# power.net
KiCad netlist of a schematic drawn in Altium Designer
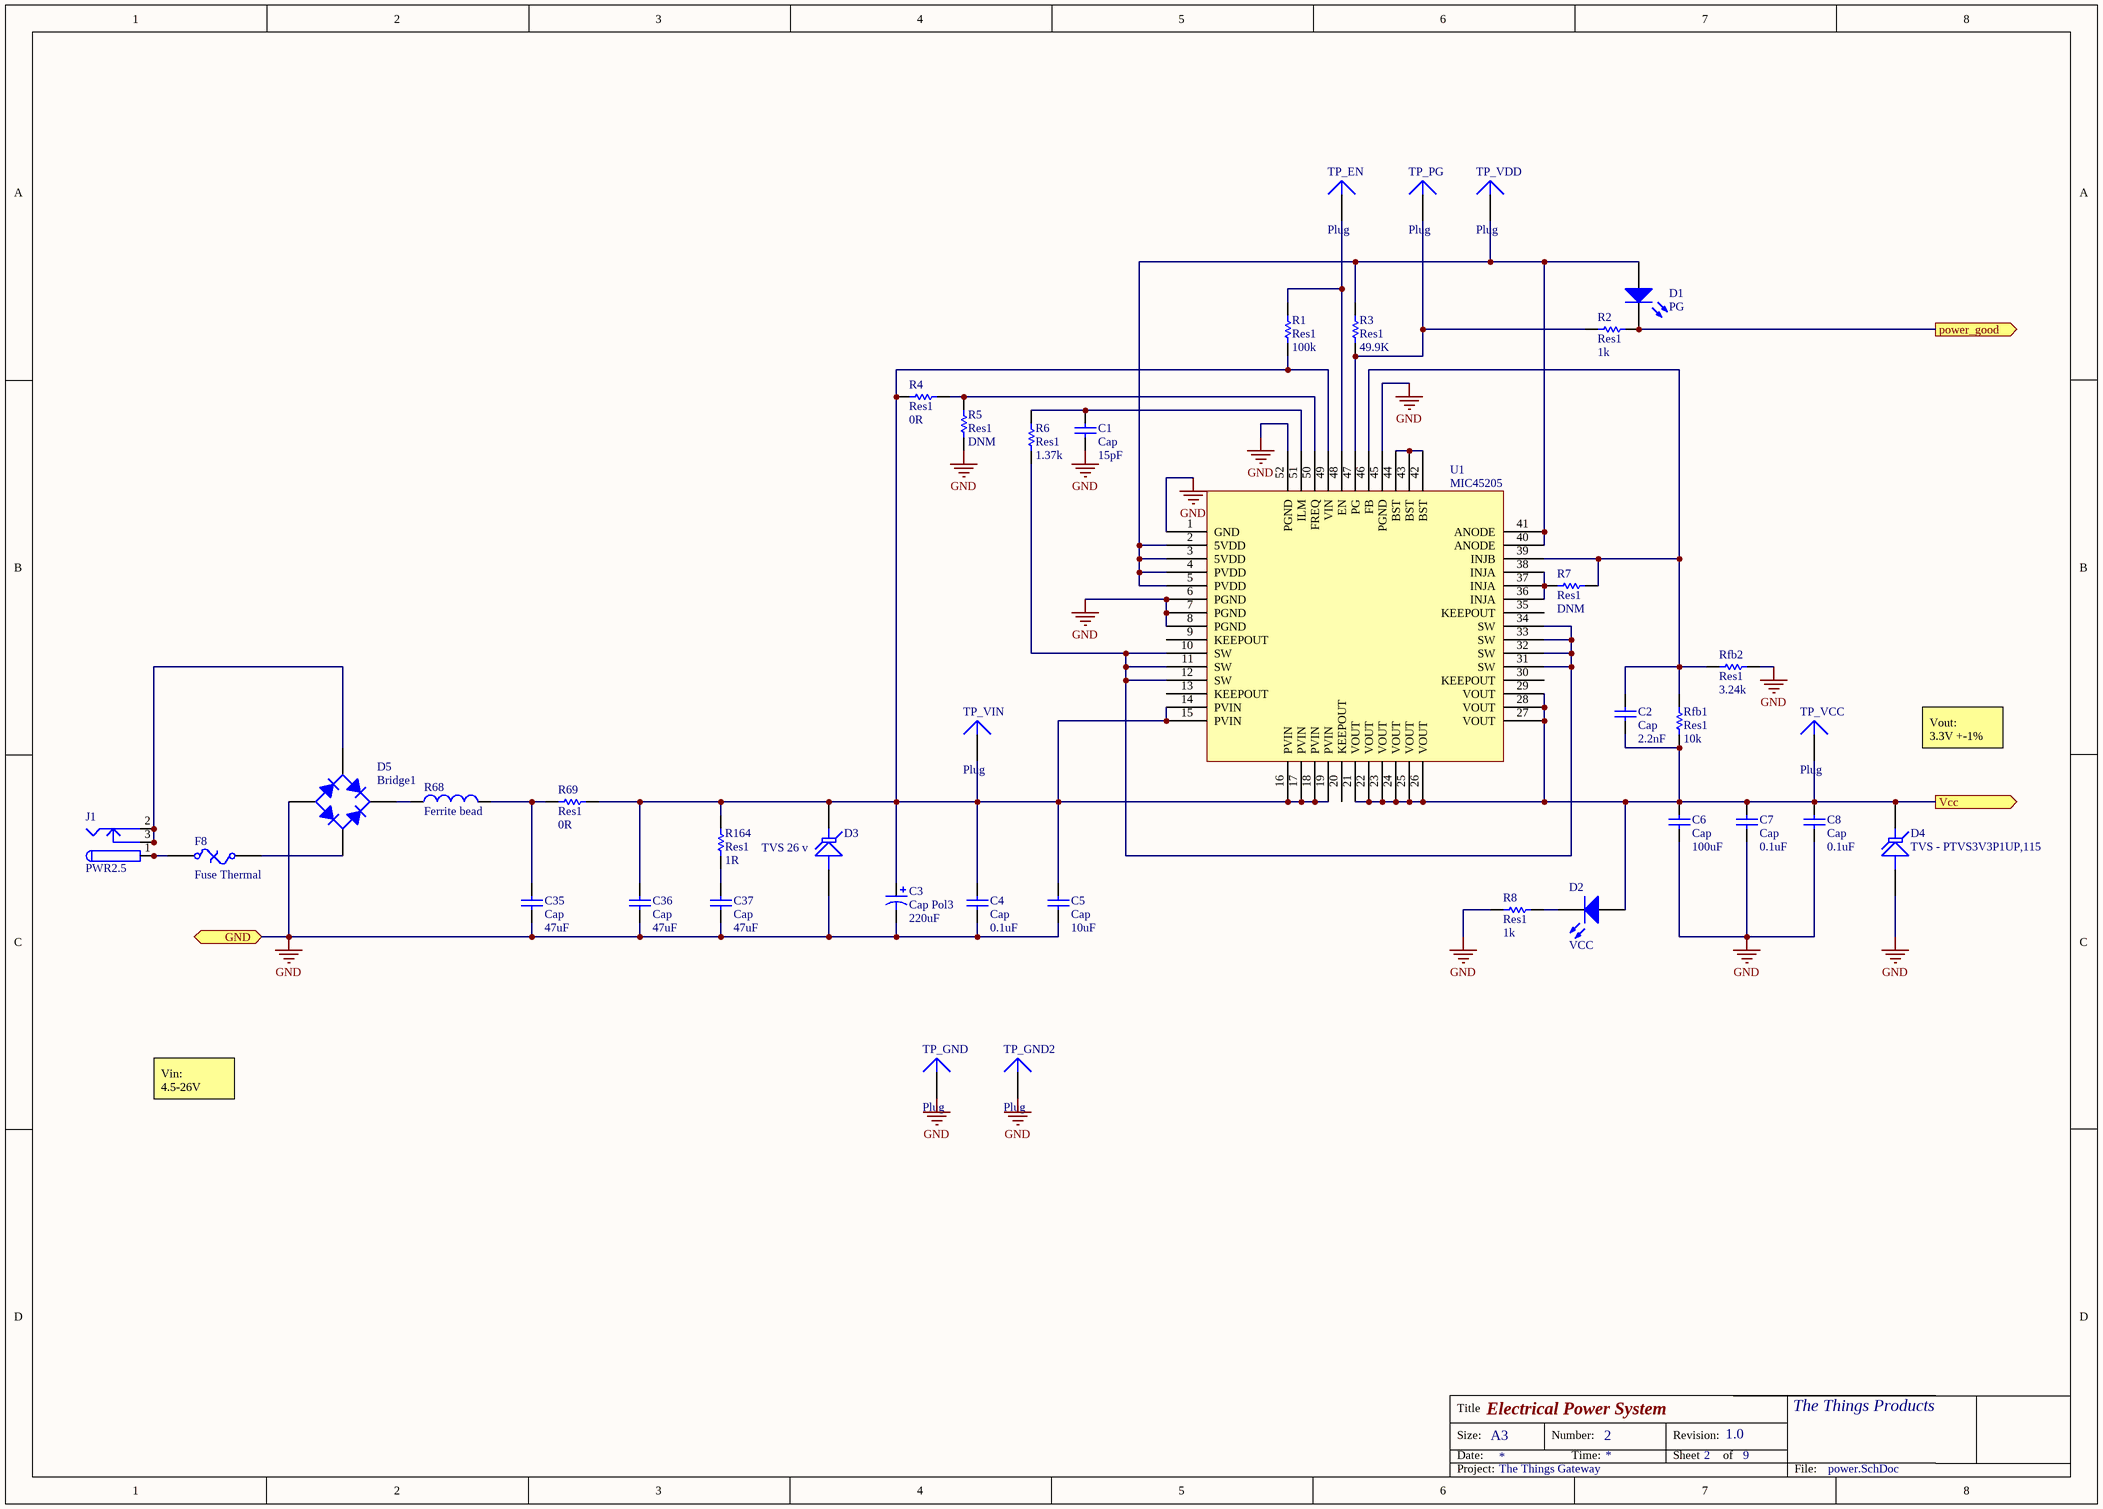
[diagram p0: power.SchDoc]

(export (version "E")
  (design (tool "Eeschema 10.0.6"))
  (components
    (comp (ref "C1")
      (value "Cap")
      (footprint "C0603")
      (description "Capacitor")
      (fields (field (name "ALTIUM_VALUE") "15pF") (field (name "PUBLISHER") "Altium Limited"))
      (libsource (lib "any") (part "Cap"))
    )
    (comp (ref "C2")
      (value "Cap")
      (footprint "C0603")
      (description "Capacitor")
      (fields (field (name "ALTIUM_VALUE") "2.2nF") (field (name "PUBLISHER") "Altium Limited"))
      (libsource (lib "any") (part "Cap"))
    )
    (comp (ref "C3")
      (value "Cap Pol3")
      (footprint "SMD_CAP_10x7.7mm_220uF - duplicate")
      (description "Polarized Capacitor (Surface Mount)")
      (fields (field (name "ALTIUM_VALUE") "220uF") (field (name "PUBLISHER") "Altium Limited"))
      (libsource (lib "Miscellaneous Devices") (part "Cap Pol3"))
    )
    (comp (ref "C4")
      (value "Cap")
      (footprint "C1206")
      (description "Capacitor")
      (fields (field (name "ALTIUM_VALUE") "0.1uF") (field (name "PUBLISHER") "Altium Limited"))
      (libsource (lib "any") (part "Cap"))
    )
    (comp (ref "C5")
      (value "Cap")
      (footprint "C1210")
      (description "Capacitor")
      (fields (field (name "ALTIUM_VALUE") "10uF") (field (name "PUBLISHER") "Altium Limited"))
      (libsource (lib "any") (part "Cap"))
    )
    (comp (ref "C6")
      (value "Cap")
      (footprint "C1210")
      (description "Capacitor")
      (fields (field (name "ALTIUM_VALUE") "100uF") (field (name "PUBLISHER") "Altium Limited"))
      (libsource (lib "any") (part "Cap"))
    )
    (comp (ref "C7")
      (value "Cap")
      (footprint "C1206")
      (description "Capacitor")
      (fields (field (name "ALTIUM_VALUE") "0.1uF") (field (name "PUBLISHER") "Altium Limited"))
      (libsource (lib "any") (part "Cap"))
    )
    (comp (ref "C8")
      (value "Cap")
      (footprint "C1206")
      (description "Capacitor")
      (fields (field (name "ALTIUM_VALUE") "0.1uF") (field (name "PUBLISHER") "Altium Limited"))
      (libsource (lib "any") (part "Cap"))
    )
    (comp (ref "C35")
      (value "Cap")
      (footprint "C1206")
      (description "Capacitor")
      (fields (field (name "ALTIUM_VALUE") "47uF") (field (name "PUBLISHER") "Altium Limited"))
      (libsource (lib "any") (part "Cap"))
    )
    (comp (ref "C36")
      (value "Cap")
      (footprint "C1206")
      (description "Capacitor")
      (fields (field (name "ALTIUM_VALUE") "47uF") (field (name "PUBLISHER") "Altium Limited"))
      (libsource (lib "any") (part "Cap"))
    )
    (comp (ref "C37")
      (value "Cap")
      (footprint "C0603")
      (description "Capacitor")
      (fields (field (name "ALTIUM_VALUE") "47uF") (field (name "PUBLISHER") "Altium Limited"))
      (libsource (lib "any") (part "Cap"))
    )
    (comp (ref "D1")
      (value "PG")
      (footprint "C0603")
      (description "Typical INFRARED GaAs LED")
      (fields (field (name "PUBLISHER") "Altium Limited"))
      (libsource (lib "any") (part "LED0"))
    )
    (comp (ref "D2")
      (value "VCC")
      (footprint "C0603")
      (description "Typical INFRARED GaAs LED")
      (fields (field (name "PUBLISHER") "Altium Limited"))
      (libsource (lib "any") (part "LED0"))
    )
    (comp (ref "D3")
      (value "TVS 26 v")
      (footprint "SOD323")
      (description "Transient Voltage Suppression (TVS) Diode")
      (fields (field (name "PUBLISHER") "Altium Limited"))
      (libsource (lib "Miscellaneous Devices") (part "Tranzorb"))
    )
    (comp (ref "D4")
      (value "TVS - PTVS3V3P1UP,115")
      (footprint "SOD323")
      (description "Transient Voltage Suppression (TVS) Diode")
      (fields (field (name "PUBLISHER") "Altium Limited"))
      (libsource (lib "Miscellaneous Devices") (part "Tranzorb"))
    )
    (comp (ref "D5")
      (value "Bridge1")
      (footprint "4-SDIP")
      (description "Full Wave Diode Bridge")
      (fields (field (name "PUBLISHER") "Altium Limited"))
      (libsource (lib "TWTG_Development") (part "Bridge1"))
    )
    (comp (ref "F8")
      (value "Fuse Thermal")
      (footprint "1812-polyfuse")
      (description "Thermal Fuse")
      (fields (field (name "PUBLISHER") "Altium Limited"))
      (libsource (lib "Any") (part "Fuse Thermal"))
    )
    (comp (ref "J1")
      (value "PWR2.5")
      (footprint "KLD-0202")
      (description "Low Voltage Power Supply Connector")
      (fields (field (name "PUBLISHER") "Altium Limited"))
      (libsource (lib "Miscellaneous Connectors") (part "PWR2.5"))
    )
    (comp (ref "R1")
      (value "Res1")
      (footprint "R0603")
      (description "Resistor")
      (fields (field (name "ALTIUM_VALUE") "100k") (field (name "PUBLISHER") "Altium Limited"))
      (libsource (lib "Miscellaneous Devices") (part "Res1"))
    )
    (comp (ref "R2")
      (value "Res1")
      (footprint "R0603")
      (description "Resistor")
      (fields (field (name "ALTIUM_VALUE") "1k") (field (name "PUBLISHER") "Altium Limited"))
      (libsource (lib "Miscellaneous Devices") (part "Res1"))
    )
    (comp (ref "R3")
      (value "Res1")
      (footprint "R0603")
      (description "Resistor")
      (fields (field (name "ALTIUM_VALUE") "49.9K") (field (name "PUBLISHER") "Altium Limited"))
      (libsource (lib "Miscellaneous Devices") (part "Res1"))
    )
    (comp (ref "R4")
      (value "Res1")
      (footprint "R0603")
      (description "Resistor")
      (fields (field (name "ALTIUM_VALUE") "0R") (field (name "PUBLISHER") "Altium Limited"))
      (libsource (lib "Miscellaneous Devices") (part "Res1"))
    )
    (comp (ref "R5")
      (value "Res1")
      (footprint "R0603")
      (description "Resistor")
      (fields (field (name "ALTIUM_VALUE") "DNM") (field (name "PUBLISHER") "Altium Limited"))
      (libsource (lib "Miscellaneous Devices") (part "Res1"))
    )
    (comp (ref "R6")
      (value "Res1")
      (footprint "R0603")
      (description "Resistor")
      (fields (field (name "ALTIUM_VALUE") "1.37k") (field (name "PUBLISHER") "Altium Limited"))
      (libsource (lib "Miscellaneous Devices") (part "Res1"))
    )
    (comp (ref "R7")
      (value "Res1")
      (footprint "R0603")
      (description "Resistor")
      (fields (field (name "ALTIUM_VALUE") "DNM") (field (name "PUBLISHER") "Altium Limited"))
      (libsource (lib "Miscellaneous Devices") (part "Res1"))
    )
    (comp (ref "R8")
      (value "Res1")
      (footprint "R0603")
      (description "Resistor")
      (fields (field (name "ALTIUM_VALUE") "1k") (field (name "PUBLISHER") "Altium Limited"))
      (libsource (lib "Miscellaneous Devices") (part "Res1"))
    )
    (comp (ref "R68")
      (value "Ferrite bead")
      (footprint "R0603")
      (description "Inductor")
      (fields (field (name "PUBLISHER") "Altium Limited"))
      (libsource (lib "Miscellaneous Devices") (part "Inductor"))
    )
    (comp (ref "R69")
      (value "Res1")
      (footprint "R0603")
      (description "Resistor")
      (fields (field (name "ALTIUM_VALUE") "0R") (field (name "PUBLISHER") "Altium Limited"))
      (libsource (lib "Miscellaneous Devices") (part "Res1"))
    )
    (comp (ref "R164")
      (value "Res1")
      (footprint "R0603")
      (description "Resistor")
      (fields (field (name "ALTIUM_VALUE") "1R") (field (name "PUBLISHER") "Altium Limited"))
      (libsource (lib "Miscellaneous Devices") (part "Res1"))
    )
    (comp (ref "Rfb1")
      (value "Res1")
      (footprint "R0603")
      (description "Resistor")
      (fields (field (name "ALTIUM_VALUE") "10k") (field (name "PUBLISHER") "Altium Limited"))
      (libsource (lib "Miscellaneous Devices") (part "Res1"))
    )
    (comp (ref "Rfb2")
      (value "Res1")
      (footprint "R0603")
      (description "Resistor")
      (fields (field (name "ALTIUM_VALUE") "3.24k") (field (name "PUBLISHER") "Altium Limited"))
      (libsource (lib "Miscellaneous Devices") (part "Res1"))
    )
    (comp (ref "TP_EN")
      (value "Plug")
      (footprint "PIN1")
      (fields (field (name "PUBLISHER") "Altium Limited"))
      (libsource (lib "Miscellaneous Connectors") (part "Plug"))
    )
    (comp (ref "TP_GND")
      (value "Plug")
      (footprint "PIN1")
      (fields (field (name "PUBLISHER") "Altium Limited"))
      (libsource (lib "Miscellaneous Connectors") (part "Plug"))
    )
    (comp (ref "TP_GND2")
      (value "Plug")
      (footprint "PIN1")
      (fields (field (name "PUBLISHER") "Altium Limited"))
      (libsource (lib "Miscellaneous Connectors") (part "Plug"))
    )
    (comp (ref "TP_PG")
      (value "Plug")
      (footprint "PIN1")
      (fields (field (name "PUBLISHER") "Altium Limited"))
      (libsource (lib "Miscellaneous Connectors") (part "Plug"))
    )
    (comp (ref "TP_VCC")
      (value "Plug")
      (footprint "PIN1")
      (fields (field (name "PUBLISHER") "Altium Limited"))
      (libsource (lib "Miscellaneous Connectors") (part "Plug"))
    )
    (comp (ref "TP_VDD")
      (value "Plug")
      (footprint "PIN1")
      (fields (field (name "PUBLISHER") "Altium Limited"))
      (libsource (lib "Miscellaneous Connectors") (part "Plug"))
    )
    (comp (ref "TP_VIN")
      (value "Plug")
      (footprint "PIN1")
      (fields (field (name "PUBLISHER") "Altium Limited"))
      (libsource (lib "Miscellaneous Connectors") (part "Plug"))
    )
    (comp (ref "U1")
      (value "MIC45205")
      (footprint "45205 Thermaly Enhanced")
      (description "MICREL45205 DC/DC Converter")
      (libsource (lib "ttn_schematic_library") (part "MIC45205"))
    )
  )
  (nets
    (net (code "1") (name "/Vcc") (class "Default")
      (node (ref "C2") (pin "1") (pinfunction "1_1") (pintype "passive"))
      (node (ref "C6") (pin "2") (pinfunction "2_2") (pintype "passive"))
      (node (ref "C7") (pin "2") (pinfunction "2_2") (pintype "passive"))
      (node (ref "C8") (pin "2") (pinfunction "2_2") (pintype "passive"))
      (node (ref "D2") (pin "1") (pinfunction "A_1") (pintype "passive"))
      (node (ref "D4") (pin "2") (pinfunction "K_2") (pintype "passive"))
      (node (ref "Rfb1") (pin "1") (pinfunction "1_1") (pintype "passive"))
      (node (ref "TP_VCC") (pin "1") (pinfunction "1_1") (pintype "passive"))
      (node (ref "U1") (pin "21") (pinfunction "VOUT_21") (pintype "passive"))
      (node (ref "U1") (pin "22") (pinfunction "VOUT_22") (pintype "passive"))
      (node (ref "U1") (pin "23") (pinfunction "VOUT_23") (pintype "passive"))
      (node (ref "U1") (pin "24") (pinfunction "VOUT_24") (pintype "passive"))
      (node (ref "U1") (pin "25") (pinfunction "VOUT_25") (pintype "passive"))
      (node (ref "U1") (pin "26") (pinfunction "VOUT_26") (pintype "passive"))
      (node (ref "U1") (pin "27") (pinfunction "VOUT_27") (pintype "passive"))
      (node (ref "U1") (pin "28") (pinfunction "VOUT_28") (pintype "passive"))
      (node (ref "U1") (pin "29") (pinfunction "VOUT_29") (pintype "passive"))
    )
    (net (code "2") (name "/power_good") (class "Default")
      (node (ref "D1") (pin "2") (pinfunction "K_2") (pintype "passive"))
      (node (ref "R2") (pin "1") (pinfunction "1_1") (pintype "passive"))
    )
    (net (code "3") (name "GND") (class "Default")
      (node (ref "C1") (pin "1") (pinfunction "1_1") (pintype "passive"))
      (node (ref "C3") (pin "2") (pinfunction "2_2") (pintype "passive"))
      (node (ref "C35") (pin "1") (pinfunction "1_1") (pintype "passive"))
      (node (ref "C36") (pin "1") (pinfunction "1_1") (pintype "passive"))
      (node (ref "C37") (pin "1") (pinfunction "1_1") (pintype "passive"))
      (node (ref "C4") (pin "1") (pinfunction "1_1") (pintype "passive"))
      (node (ref "C5") (pin "1") (pinfunction "1_1") (pintype "passive"))
      (node (ref "C6") (pin "1") (pinfunction "1_1") (pintype "passive"))
      (node (ref "C7") (pin "1") (pinfunction "1_1") (pintype "passive"))
      (node (ref "C8") (pin "1") (pinfunction "1_1") (pintype "passive"))
      (node (ref "D3") (pin "1") (pinfunction "A_1") (pintype "passive"))
      (node (ref "D4") (pin "1") (pinfunction "A_1") (pintype "passive"))
      (node (ref "D5") (pin "2") (pinfunction "A_2") (pintype "passive"))
      (node (ref "R5") (pin "2") (pinfunction "2_2") (pintype "passive"))
      (node (ref "R8") (pin "1") (pinfunction "1_1") (pintype "passive"))
      (node (ref "Rfb2") (pin "1") (pinfunction "1_1") (pintype "passive"))
      (node (ref "TP_GND") (pin "1") (pinfunction "1_1") (pintype "passive"))
      (node (ref "TP_GND2") (pin "1") (pinfunction "1_1") (pintype "passive"))
      (node (ref "U1") (pin "1") (pinfunction "GND_1") (pintype "passive"))
      (node (ref "U1") (pin "45") (pinfunction "PGND_45") (pintype "passive"))
      (node (ref "U1") (pin "52") (pinfunction "PGND_52") (pintype "passive"))
      (node (ref "U1") (pin "6") (pinfunction "PGND_6") (pintype "passive"))
      (node (ref "U1") (pin "7") (pinfunction "PGND_7") (pintype "passive"))
      (node (ref "U1") (pin "8") (pinfunction "PGND_8") (pintype "passive"))
    )
    (net (code "4") (name "Net-(C35-Pad2)") (class "Default")
      (node (ref "C35") (pin "2") (pinfunction "2_2") (pintype "passive"))
      (node (ref "R68") (pin "2") (pinfunction "2_2") (pintype "passive"))
      (node (ref "R69") (pin "2") (pinfunction "2_2") (pintype "passive"))
    )
    (net (code "5") (name "Net-(C37-Pad2)") (class "Default")
      (node (ref "C37") (pin "2") (pinfunction "2_2") (pintype "passive"))
      (node (ref "R164") (pin "2") (pinfunction "2_2") (pintype "passive"))
    )
    (net (code "6") (name "Net-(D1-A)") (class "Default")
      (node (ref "D1") (pin "1") (pinfunction "A_1") (pintype "passive"))
      (node (ref "R3") (pin "1") (pinfunction "1_1") (pintype "passive"))
      (node (ref "TP_VDD") (pin "1") (pinfunction "1_1") (pintype "passive"))
      (node (ref "U1") (pin "2") (pinfunction "5VDD_2") (pintype "passive"))
      (node (ref "U1") (pin "3") (pinfunction "5VDD_3") (pintype "passive"))
      (node (ref "U1") (pin "4") (pinfunction "PVDD_4") (pintype "passive"))
      (node (ref "U1") (pin "40") (pinfunction "ANODE_40") (pintype "passive"))
      (node (ref "U1") (pin "41") (pinfunction "ANODE_41") (pintype "passive"))
      (node (ref "U1") (pin "5") (pinfunction "PVDD_5") (pintype "passive"))
    )
    (net (code "7") (name "Net-(D2-K)") (class "Default")
      (node (ref "D2") (pin "2") (pinfunction "K_2") (pintype "passive"))
      (node (ref "R8") (pin "2") (pinfunction "2_2") (pintype "passive"))
    )
    (net (code "8") (name "Net-(D3-K)") (class "Default")
      (node (ref "C3") (pin "1") (pinfunction "1_1") (pintype "passive"))
      (node (ref "C36") (pin "2") (pinfunction "2_2") (pintype "passive"))
      (node (ref "C4") (pin "2") (pinfunction "2_2") (pintype "passive"))
      (node (ref "C5") (pin "2") (pinfunction "2_2") (pintype "passive"))
      (node (ref "D3") (pin "2") (pinfunction "K_2") (pintype "passive"))
      (node (ref "R1") (pin "1") (pinfunction "1_1") (pintype "passive"))
      (node (ref "R164") (pin "1") (pinfunction "1_1") (pintype "passive"))
      (node (ref "R4") (pin "2") (pinfunction "2_2") (pintype "passive"))
      (node (ref "R69") (pin "1") (pinfunction "1_1") (pintype "passive"))
      (node (ref "TP_VIN") (pin "1") (pinfunction "1_1") (pintype "passive"))
      (node (ref "U1") (pin "14") (pinfunction "PVIN_14") (pintype "passive"))
      (node (ref "U1") (pin "15") (pinfunction "PVIN_15") (pintype "passive"))
      (node (ref "U1") (pin "16") (pinfunction "PVIN_16") (pintype "passive"))
      (node (ref "U1") (pin "17") (pinfunction "PVIN_17") (pintype "passive"))
      (node (ref "U1") (pin "18") (pinfunction "PVIN_18") (pintype "passive"))
      (node (ref "U1") (pin "19") (pinfunction "PVIN_19") (pintype "passive"))
      (node (ref "U1") (pin "49") (pinfunction "VIN_49") (pintype "passive"))
    )
    (net (code "9") (name "Net-(D5-C-Pad3)") (class "Default")
      (node (ref "D5") (pin "3") (pinfunction "C_3") (pintype "passive"))
      (node (ref "J1") (pin "2") (pinfunction "2_2") (pintype "power_in"))
      (node (ref "J1") (pin "2A") (pinfunction "2A_2A") (pintype "power_in"))
      (node (ref "J1") (pin "2B") (pinfunction "2B_2B") (pintype "power_in"))
      (node (ref "J1") (pin "3") (pinfunction "3_3") (pintype "power_in"))
      (node (ref "J1") (pin "3A") (pinfunction "3A_3A") (pintype "power_in"))
      (node (ref "J1") (pin "3B") (pinfunction "3B_3B") (pintype "power_in"))
    )
    (net (code "10") (name "Net-(D5-C-Pad4)") (class "Default")
      (node (ref "D5") (pin "4") (pinfunction "C_4") (pintype "passive"))
      (node (ref "F8") (pin "2") (pinfunction "2_2") (pintype "passive"))
    )
    (net (code "11") (name "Net-(D5-K)") (class "Default")
      (node (ref "D5") (pin "1") (pinfunction "K_1") (pintype "passive"))
      (node (ref "R68") (pin "1") (pinfunction "1_1") (pintype "passive"))
    )
    (net (code "12") (name "Net-(F8-Pad1)") (class "Default")
      (node (ref "F8") (pin "1") (pinfunction "1_1") (pintype "passive"))
      (node (ref "J1") (pin "1") (pinfunction "1_1") (pintype "power_in"))
      (node (ref "J1") (pin "1A") (pinfunction "1A_1A") (pintype "power_in"))
      (node (ref "J1") (pin "1B") (pinfunction "1B_1B") (pintype "power_in"))
    )
    (net (code "13") (name "Net-(R6-Pad1)") (class "Default")
      (node (ref "R6") (pin "1") (pinfunction "1_1") (pintype "passive"))
      (node (ref "U1") (pin "10") (pinfunction "SW_10") (pintype "passive"))
      (node (ref "U1") (pin "11") (pinfunction "SW_11") (pintype "passive"))
      (node (ref "U1") (pin "12") (pinfunction "SW_12") (pintype "passive"))
      (node (ref "U1") (pin "31") (pinfunction "SW_31") (pintype "passive"))
      (node (ref "U1") (pin "32") (pinfunction "SW_32") (pintype "passive"))
      (node (ref "U1") (pin "33") (pinfunction "SW_33") (pintype "passive"))
      (node (ref "U1") (pin "34") (pinfunction "SW_34") (pintype "passive"))
    )
    (net (code "14") (name "Net-(R7-Pad2)") (class "Default")
      (node (ref "R7") (pin "2") (pinfunction "2_2") (pintype "passive"))
      (node (ref "U1") (pin "36") (pinfunction "INJA_36") (pintype "passive"))
      (node (ref "U1") (pin "37") (pinfunction "INJA_37") (pintype "passive"))
      (node (ref "U1") (pin "38") (pinfunction "INJA_38") (pintype "passive"))
    )
    (net (code "15") (name "Net-(U1-BST-Pad42)") (class "Default")
      (node (ref "U1") (pin "42") (pinfunction "BST_42") (pintype "passive"))
      (node (ref "U1") (pin "43") (pinfunction "BST_43") (pintype "passive"))
      (node (ref "U1") (pin "44") (pinfunction "BST_44") (pintype "passive"))
    )
    (net (code "16") (name "Net-(U1-EN)") (class "Default")
      (node (ref "R1") (pin "2") (pinfunction "2_2") (pintype "passive"))
      (node (ref "TP_EN") (pin "1") (pinfunction "1_1") (pintype "passive"))
      (node (ref "U1") (pin "48") (pinfunction "EN_48") (pintype "passive"))
    )
    (net (code "17") (name "Net-(U1-FB)") (class "Default")
      (node (ref "C2") (pin "2") (pinfunction "2_2") (pintype "passive"))
      (node (ref "R7") (pin "1") (pinfunction "1_1") (pintype "passive"))
      (node (ref "Rfb1") (pin "2") (pinfunction "2_2") (pintype "passive"))
      (node (ref "Rfb2") (pin "2") (pinfunction "2_2") (pintype "passive"))
      (node (ref "U1") (pin "39") (pinfunction "INJB_39") (pintype "passive"))
      (node (ref "U1") (pin "46") (pinfunction "FB_46") (pintype "passive"))
    )
    (net (code "18") (name "Net-(U1-FREQ)") (class "Default")
      (node (ref "R4") (pin "1") (pinfunction "1_1") (pintype "passive"))
      (node (ref "R5") (pin "1") (pinfunction "1_1") (pintype "passive"))
      (node (ref "U1") (pin "50") (pinfunction "FREQ_50") (pintype "passive"))
    )
    (net (code "19") (name "Net-(U1-ILM)") (class "Default")
      (node (ref "C1") (pin "2") (pinfunction "2_2") (pintype "passive"))
      (node (ref "R6") (pin "2") (pinfunction "2_2") (pintype "passive"))
      (node (ref "U1") (pin "51") (pinfunction "ILM_51") (pintype "passive"))
    )
    (net (code "20") (name "Net-(U1-PG)") (class "Default")
      (node (ref "R2") (pin "2") (pinfunction "2_2") (pintype "passive"))
      (node (ref "R3") (pin "2") (pinfunction "2_2") (pintype "passive"))
      (node (ref "TP_PG") (pin "1") (pinfunction "1_1") (pintype "passive"))
      (node (ref "U1") (pin "47") (pinfunction "PG_47") (pintype "passive"))
    )
    (net (code "21") (name "unconnected-(U1-KEEPOUT-Pad9)") (class "Default")
      (node (ref "U1") (pin "9") (pinfunction "KEEPOUT_9") (pintype "passive"))
    )
    (net (code "22") (name "unconnected-(U1-KEEPOUT-Pad13)") (class "Default")
      (node (ref "U1") (pin "13") (pinfunction "KEEPOUT_13") (pintype "passive"))
    )
    (net (code "23") (name "unconnected-(U1-KEEPOUT-Pad20)") (class "Default")
      (node (ref "U1") (pin "20") (pinfunction "KEEPOUT_20") (pintype "passive"))
    )
    (net (code "24") (name "unconnected-(U1-KEEPOUT-Pad30)") (class "Default")
      (node (ref "U1") (pin "30") (pinfunction "KEEPOUT_30") (pintype "passive"))
    )
    (net (code "25") (name "unconnected-(U1-KEEPOUT-Pad35)") (class "Default")
      (node (ref "U1") (pin "35") (pinfunction "KEEPOUT_35") (pintype "passive"))
    )
  )
)
